# Ganancia.net
KiCad netlist of a schematic drawn in Altium Designer
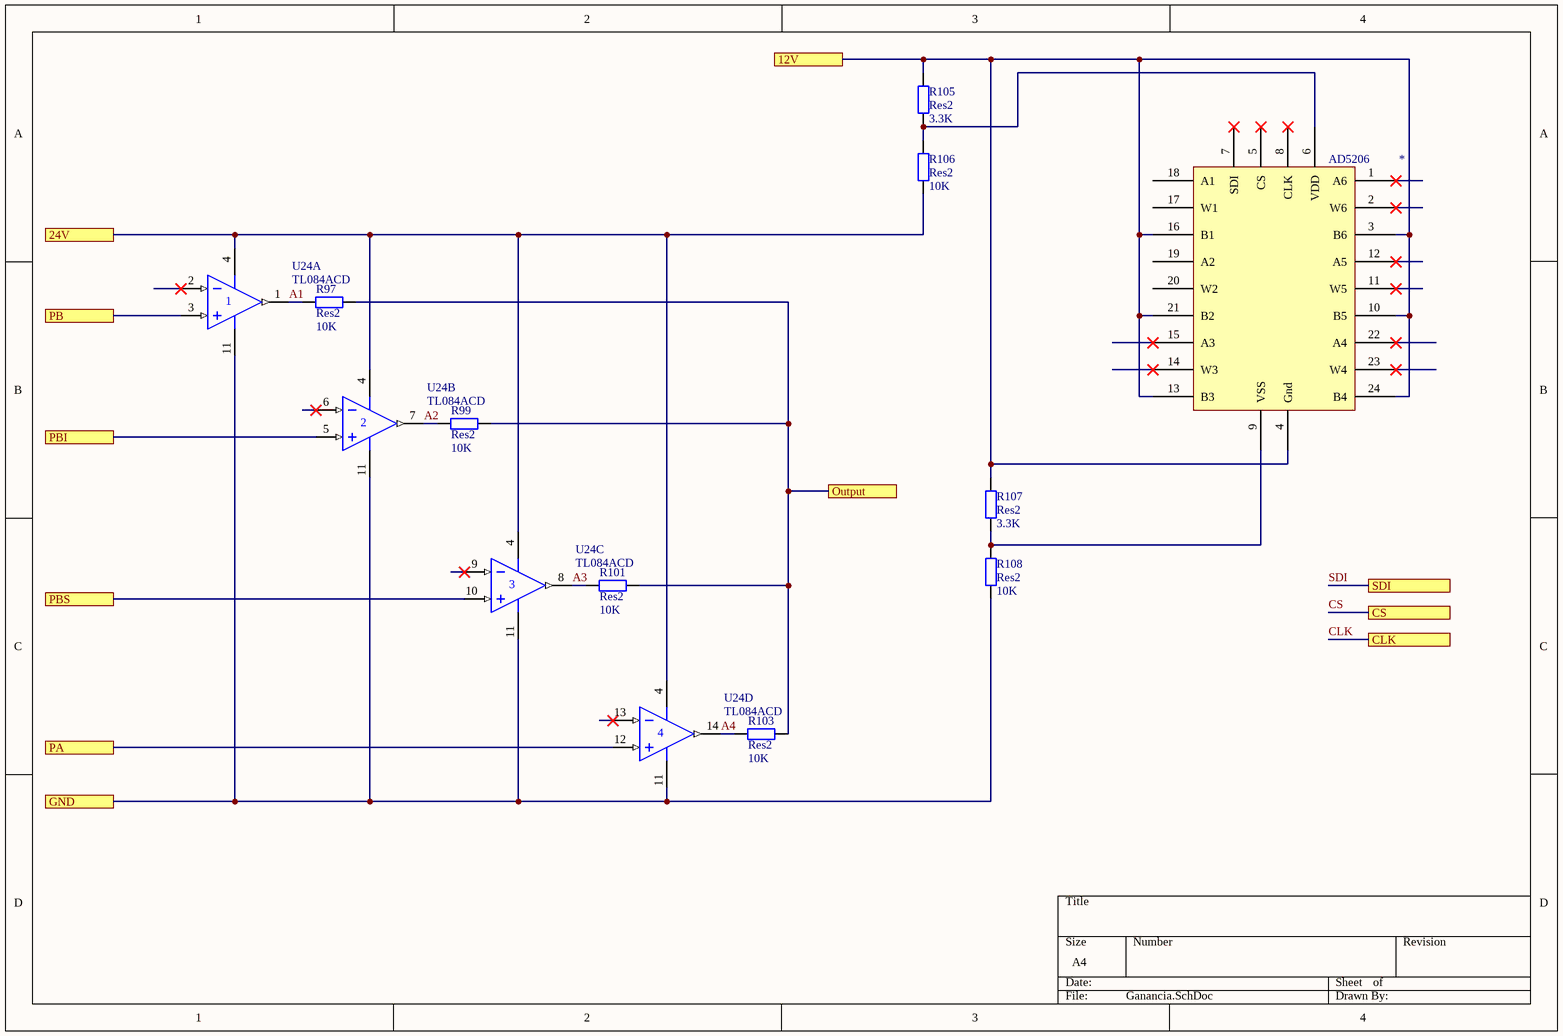
[diagram p0: Ganancia.SchDoc]

(export (version "E")
  (design (tool "Eeschema 10.0.6"))
  (components
    (comp (ref "*") (value "AD5206") (footprint "DIP-24/D31") (libsource (lib "XR2206") (part "AD5206")))
    (comp (ref "R97")
      (value "Res2")
      (footprint "1206 resistor")
      (description "Resistor")
      (fields (field (name "ALTIUM_VALUE") "10K") (field (name "PUBLISHER") "Altium Limited"))
      (libsource (lib "") (part "Res2_1"))
    )
    (comp (ref "R99")
      (value "Res2")
      (footprint "1206 resistor")
      (description "Resistor")
      (fields (field (name "ALTIUM_VALUE") "10K") (field (name "PUBLISHER") "Altium Limited"))
      (libsource (lib "") (part "Res2_1"))
    )
    (comp (ref "R101")
      (value "Res2")
      (footprint "1206 resistor")
      (description "Resistor")
      (fields (field (name "ALTIUM_VALUE") "10K") (field (name "PUBLISHER") "Altium Limited"))
      (libsource (lib "") (part "Res2_1"))
    )
    (comp (ref "R103")
      (value "Res2")
      (footprint "1206 resistor")
      (description "Resistor")
      (fields (field (name "ALTIUM_VALUE") "10K") (field (name "PUBLISHER") "Altium Limited"))
      (libsource (lib "") (part "Res2_1"))
    )
    (comp (ref "R105")
      (value "Res2")
      (footprint "1206 resistor")
      (description "Resistor")
      (fields (field (name "ALTIUM_VALUE") "3.3K") (field (name "PUBLISHER") "Altium Limited"))
      (libsource (lib "Miscellaneous Devices") (part "Res2"))
    )
    (comp (ref "R106")
      (value "Res2")
      (footprint "1206 resistor")
      (description "Resistor")
      (fields (field (name "ALTIUM_VALUE") "10K") (field (name "PUBLISHER") "Altium Limited"))
      (libsource (lib "Miscellaneous Devices") (part "Res2"))
    )
    (comp (ref "R107")
      (value "Res2")
      (footprint "1206 resistor")
      (description "Resistor")
      (fields (field (name "ALTIUM_VALUE") "3.3K") (field (name "PUBLISHER") "Altium Limited"))
      (libsource (lib "Miscellaneous Devices") (part "Res2"))
    )
    (comp (ref "R108")
      (value "Res2")
      (footprint "1206 resistor")
      (description "Resistor")
      (fields (field (name "ALTIUM_VALUE") "10K") (field (name "PUBLISHER") "Altium Limited"))
      (libsource (lib "Miscellaneous Devices") (part "Res2"))
    )
    (comp (ref "U24")
      (value "TL084ACD")
      (footprint "751A-02_N")
      (description "JFET-Input Operational Amplifier")
      (fields (field (name "PUBLISHER") "Altium Limited"))
      (libsource (lib "Motorola Amplifier Operational Amplifier") (part "TL084ACD"))
    )
  )
  (nets
    (net (code "1") (name "/12V") (class "Default")
      (node (ref "*") (pin "10") (pinfunction "B5_10") (pintype "passive"))
      (node (ref "*") (pin "13") (pinfunction "B3_13") (pintype "passive"))
      (node (ref "*") (pin "16") (pinfunction "B1_16") (pintype "passive"))
      (node (ref "*") (pin "21") (pinfunction "B2_21") (pintype "passive"))
      (node (ref "*") (pin "24") (pinfunction "B4_24") (pintype "passive"))
      (node (ref "*") (pin "3") (pinfunction "B6_3") (pintype "passive"))
      (node (ref "*") (pin "4") (pinfunction "Gnd_4") (pintype "passive"))
      (node (ref "R105") (pin "2") (pinfunction "2_2") (pintype "passive"))
      (node (ref "R107") (pin "2") (pinfunction "2_2") (pintype "passive"))
    )
    (net (code "2") (name "/24V") (class "Default")
      (node (ref "R106") (pin "1") (pinfunction "1_1") (pintype "passive"))
      (node (ref "U24") (pin "4") (pinfunction "V+_4") (pintype "power_in"))
    )
    (net (code "3") (name "/A1") (class "Default")
      (node (ref "R97") (pin "1") (pinfunction "1_1") (pintype "passive"))
      (node (ref "U24") (pin "1") (pinfunction "OUT_1") (pintype "output"))
    )
    (net (code "4") (name "/A2") (class "Default")
      (node (ref "R99") (pin "1") (pinfunction "1_1") (pintype "passive"))
      (node (ref "U24") (pin "7") (pinfunction "OUT_7") (pintype "output"))
    )
    (net (code "5") (name "/A3") (class "Default")
      (node (ref "R101") (pin "1") (pinfunction "1_1") (pintype "passive"))
      (node (ref "U24") (pin "8") (pinfunction "OUT_8") (pintype "output"))
    )
    (net (code "6") (name "/A4") (class "Default")
      (node (ref "R103") (pin "1") (pinfunction "1_1") (pintype "passive"))
      (node (ref "U24") (pin "14") (pinfunction "OUT_14") (pintype "output"))
    )
    (net (code "9") (name "/GND") (class "Default")
      (node (ref "R108") (pin "1") (pinfunction "1_1") (pintype "passive"))
      (node (ref "U24") (pin "11") (pinfunction "V-_11") (pintype "power_in"))
    )
    (net (code "10") (name "/Output") (class "Default")
      (node (ref "R101") (pin "2") (pinfunction "2_2") (pintype "passive"))
      (node (ref "R103") (pin "2") (pinfunction "2_2") (pintype "passive"))
      (node (ref "R97") (pin "2") (pinfunction "2_2") (pintype "passive"))
      (node (ref "R99") (pin "2") (pinfunction "2_2") (pintype "passive"))
    )
    (net (code "11") (name "/PA") (class "Default")
      (node (ref "U24") (pin "12") (pinfunction "IN+_12") (pintype "input"))
    )
    (net (code "12") (name "/PB") (class "Default")
      (node (ref "U24") (pin "3") (pinfunction "IN+_3") (pintype "input"))
    )
    (net (code "13") (name "/PBI") (class "Default")
      (node (ref "U24") (pin "5") (pinfunction "IN+_5") (pintype "input"))
    )
    (net (code "14") (name "/PBS") (class "Default")
      (node (ref "U24") (pin "10") (pinfunction "IN+_10") (pintype "input"))
    )
    (net (code "16") (name "Net-(*-VDD)") (class "Default")
      (node (ref "*") (pin "6") (pinfunction "VDD_6") (pintype "passive"))
      (node (ref "R105") (pin "1") (pinfunction "1_1") (pintype "passive"))
      (node (ref "R106") (pin "2") (pinfunction "2_2") (pintype "passive"))
    )
    (net (code "17") (name "Net-(*-VSS)") (class "Default")
      (node (ref "*") (pin "9") (pinfunction "VSS_9") (pintype "passive"))
      (node (ref "R107") (pin "1") (pinfunction "1_1") (pintype "passive"))
      (node (ref "R108") (pin "2") (pinfunction "2_2") (pintype "passive"))
    )
    (net (code "18") (name "unconnected-(*-A1-Pad18)") (class "Default")
      (node (ref "*") (pin "18") (pinfunction "A1_18") (pintype "passive"))
    )
    (net (code "19") (name "unconnected-(*-A2-Pad19)") (class "Default")
      (node (ref "*") (pin "19") (pinfunction "A2_19") (pintype "passive"))
    )
    (net (code "20") (name "unconnected-(*-A3-Pad15)") (class "Default")
      (node (ref "*") (pin "15") (pinfunction "A3_15") (pintype "passive+no_connect"))
    )
    (net (code "21") (name "unconnected-(*-A4-Pad22)") (class "Default")
      (node (ref "*") (pin "22") (pinfunction "A4_22") (pintype "passive+no_connect"))
    )
    (net (code "22") (name "unconnected-(*-A5-Pad12)") (class "Default")
      (node (ref "*") (pin "12") (pinfunction "A5_12") (pintype "passive+no_connect"))
    )
    (net (code "23") (name "unconnected-(*-A6-Pad1)") (class "Default")
      (node (ref "*") (pin "1") (pinfunction "A6_1") (pintype "passive+no_connect"))
    )
    (net (code "24") (name "unconnected-(*-CLK-Pad8)") (class "Default")
      (node (ref "*") (pin "8") (pinfunction "CLK_8") (pintype "passive+no_connect"))
    )
    (net (code "25") (name "unconnected-(*-CS-Pad5)") (class "Default")
      (node (ref "*") (pin "5") (pinfunction "CS_5") (pintype "passive+no_connect"))
    )
    (net (code "26") (name "unconnected-(*-SDI-Pad7)") (class "Default")
      (node (ref "*") (pin "7") (pinfunction "SDI_7") (pintype "passive+no_connect"))
    )
    (net (code "27") (name "unconnected-(*-W1-Pad17)") (class "Default")
      (node (ref "*") (pin "17") (pinfunction "W1_17") (pintype "passive"))
    )
    (net (code "28") (name "unconnected-(*-W2-Pad20)") (class "Default")
      (node (ref "*") (pin "20") (pinfunction "W2_20") (pintype "passive"))
    )
    (net (code "29") (name "unconnected-(*-W3-Pad14)") (class "Default")
      (node (ref "*") (pin "14") (pinfunction "W3_14") (pintype "passive+no_connect"))
    )
    (net (code "30") (name "unconnected-(*-W4-Pad23)") (class "Default")
      (node (ref "*") (pin "23") (pinfunction "W4_23") (pintype "passive+no_connect"))
    )
    (net (code "31") (name "unconnected-(*-W5-Pad11)") (class "Default")
      (node (ref "*") (pin "11") (pinfunction "W5_11") (pintype "passive+no_connect"))
    )
    (net (code "32") (name "unconnected-(*-W6-Pad2)") (class "Default")
      (node (ref "*") (pin "2") (pinfunction "W6_2") (pintype "passive+no_connect"))
    )
    (net (code "33") (name "unconnected-(U24A-IN--Pad2)") (class "Default")
      (node (ref "U24") (pin "2") (pinfunction "IN-_2") (pintype "input+no_connect"))
    )
    (net (code "34") (name "unconnected-(U24B-IN--Pad6)") (class "Default")
      (node (ref "U24") (pin "6") (pinfunction "IN-_6") (pintype "input+no_connect"))
    )
    (net (code "35") (name "unconnected-(U24C-IN--Pad9)") (class "Default")
      (node (ref "U24") (pin "9") (pinfunction "IN-_9") (pintype "input+no_connect"))
    )
    (net (code "36") (name "unconnected-(U24D-IN--Pad13)") (class "Default")
      (node (ref "U24") (pin "13") (pinfunction "IN-_13") (pintype "input+no_connect"))
    )
  )
)
